# Sequencer-V02-023.net
KiCad netlist of a schematic drawn in EAGLE
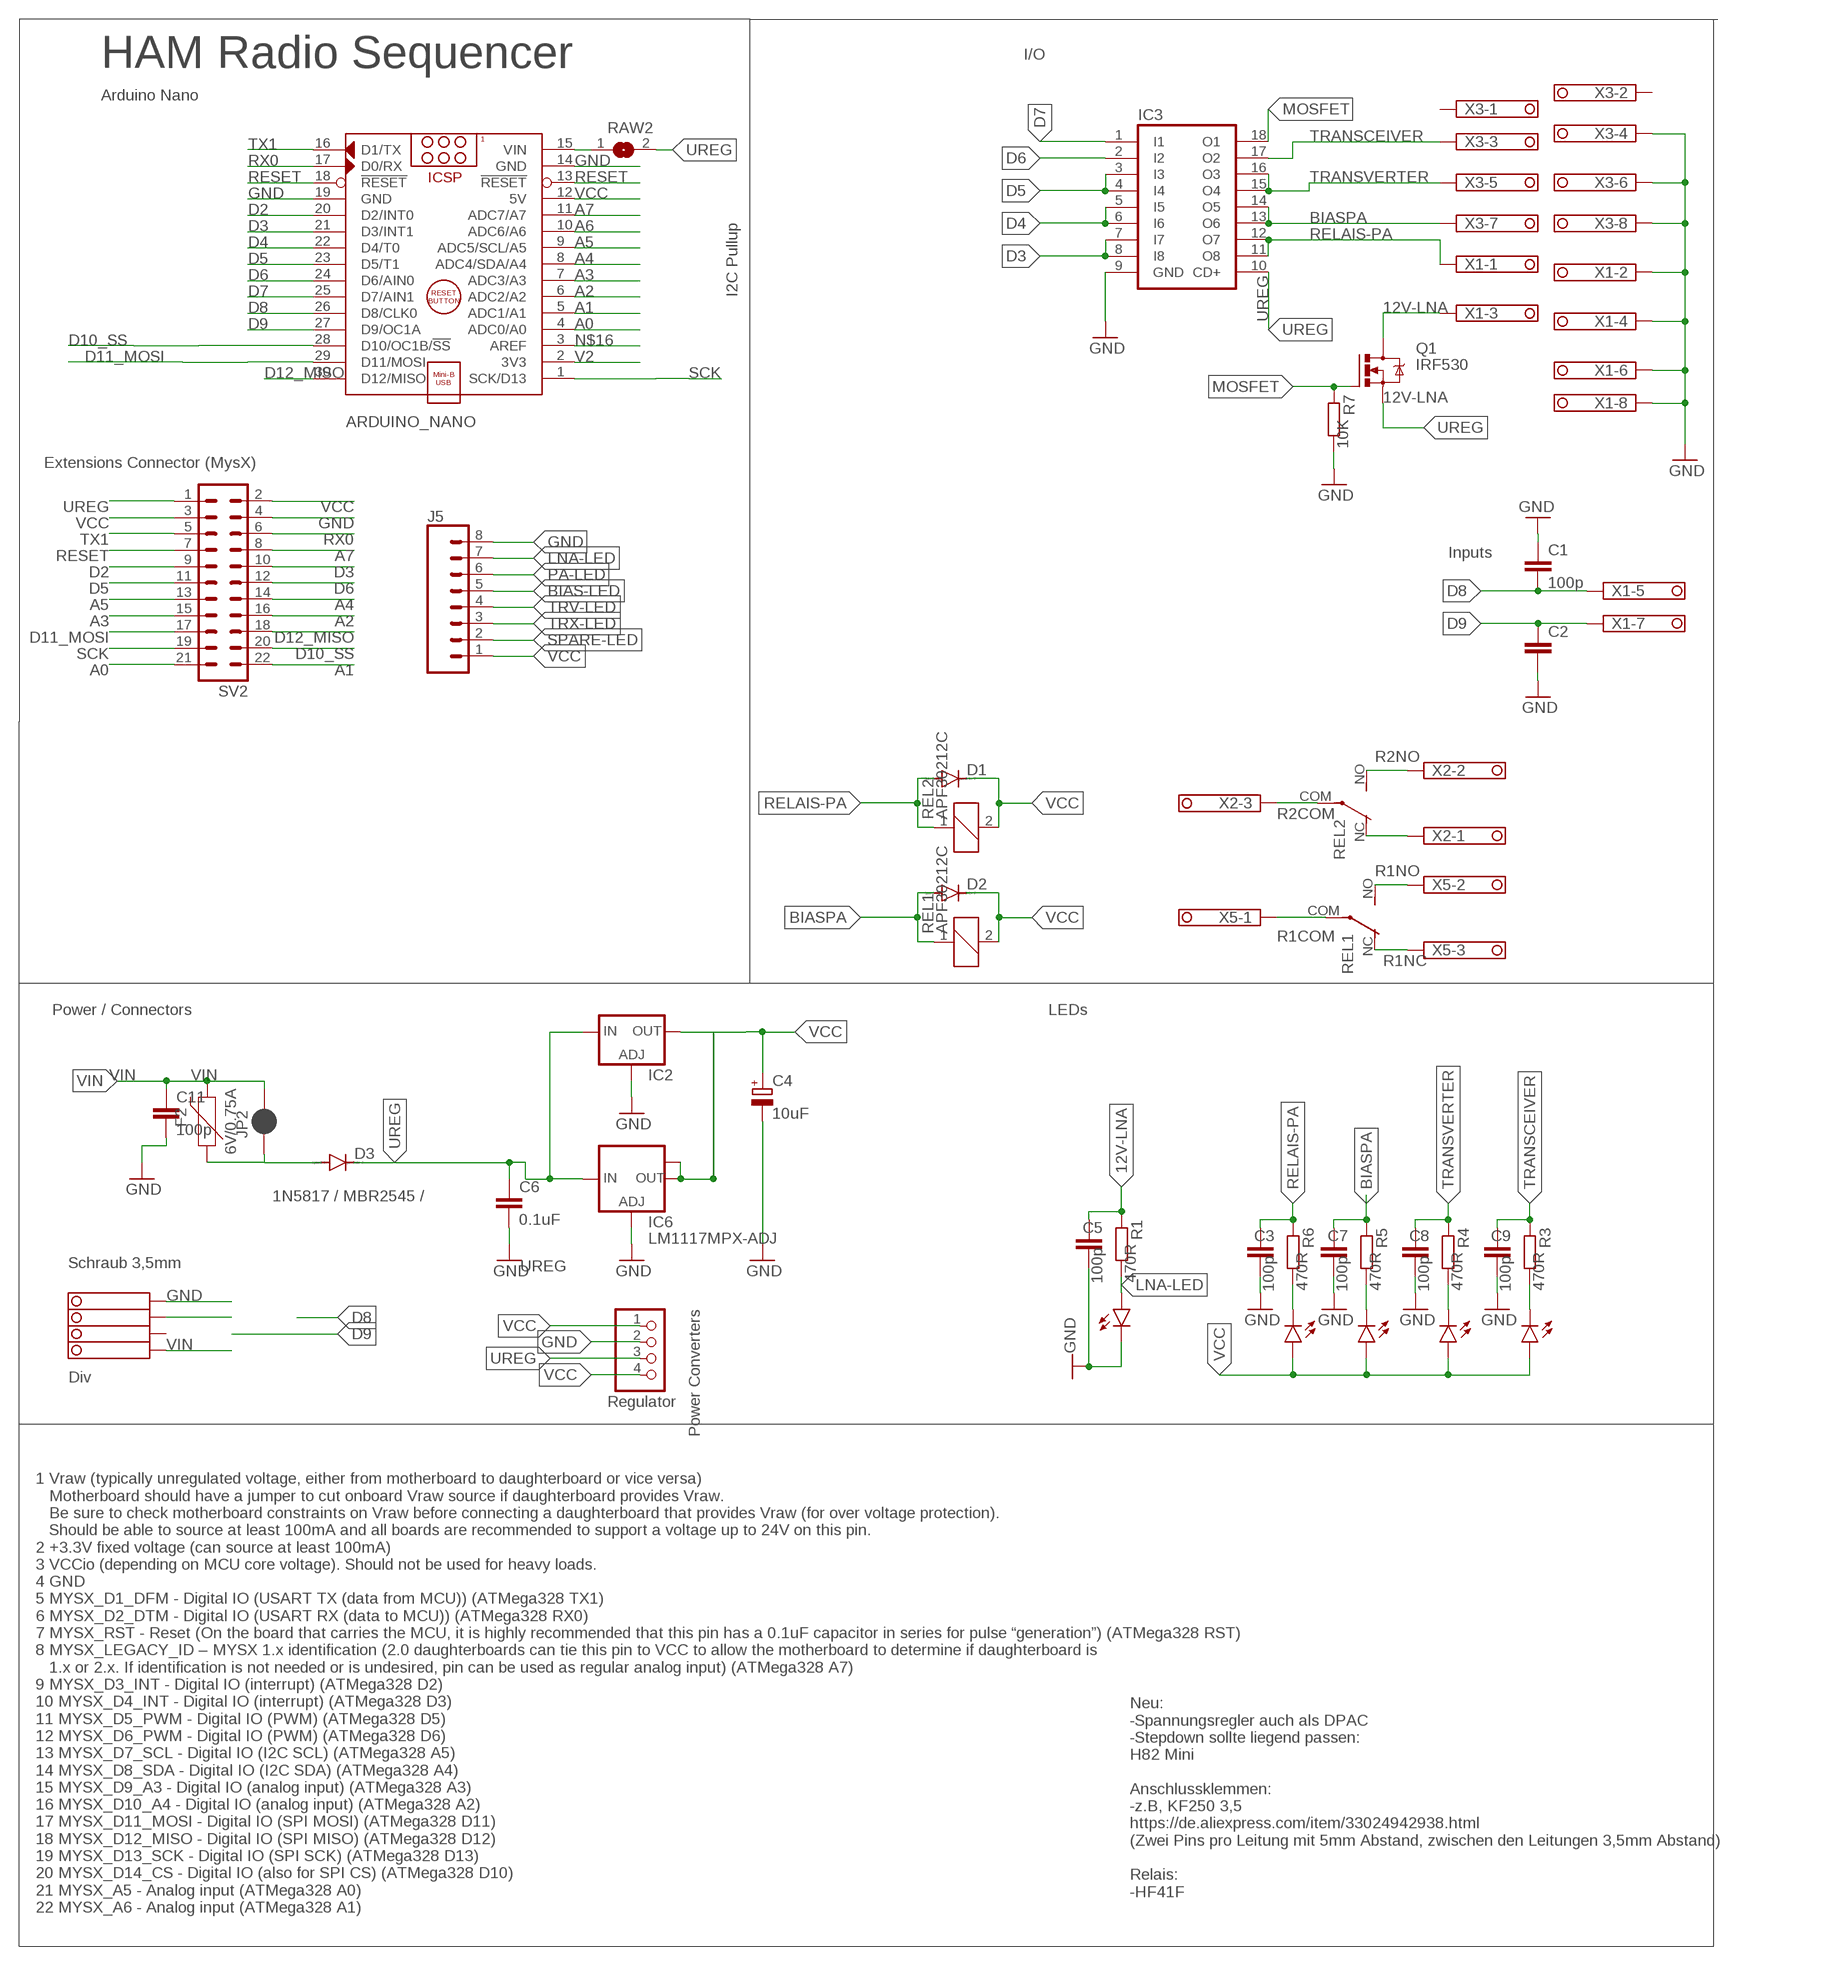
[diagram p0: schematic, sheet 1]

(export (version "E")
  (design (tool "Eeschema 10.0.6"))
  (components
    (comp (ref "ARDUINO_NANO")
      (value "ARDUINO_NANO_OHNE-BOHR")
      (footprint "eagle-import:ARDUINO_NANO")
      (libsource (lib "eagle-import") (part "ARDUINO_NANO_OHNE-BOHR"))
    )
    (comp (ref "C1")
      (value "100p")
      (footprint "eagle-import:C025-025X050")
      (libsource (lib "eagle-import") (part "C-EU025-025X050"))
    )
    (comp (ref "C2")
      (value "C-EU025-025X050")
      (footprint "eagle-import:C025-025X050")
      (libsource (lib "eagle-import") (part "C-EU025-025X050"))
    )
    (comp (ref "C3")
      (value "100p")
      (footprint "eagle-import:C025-025X050")
      (libsource (lib "eagle-import") (part "C-EU025-025X050"))
    )
    (comp (ref "C4")
      (value "10uF")
      (footprint "eagle-import:E3,5-8")
      (libsource (lib "eagle-import") (part "CPOL-EUE3.5-8"))
    )
    (comp (ref "C5")
      (value "100p")
      (footprint "eagle-import:C025-025X050")
      (libsource (lib "eagle-import") (part "C-EU025-025X050"))
    )
    (comp (ref "C6")
      (value "0.1uF")
      (footprint "eagle-import:C050-024X044")
      (libsource (lib "eagle-import") (part "C-EU050-024X044"))
    )
    (comp (ref "C7")
      (value "100p")
      (footprint "eagle-import:C025-025X050")
      (libsource (lib "eagle-import") (part "C-EU025-025X050"))
    )
    (comp (ref "C8")
      (value "100p")
      (footprint "eagle-import:C025-025X050")
      (libsource (lib "eagle-import") (part "C-EU025-025X050"))
    )
    (comp (ref "C9")
      (value "100p")
      (footprint "eagle-import:C025-025X050")
      (libsource (lib "eagle-import") (part "C-EU025-025X050"))
    )
    (comp (ref "C11")
      (value "100p")
      (footprint "eagle-import:C025-025X050")
      (libsource (lib "eagle-import") (part "C-EU025-025X050"))
    )
    (comp (ref "D1")
      (value "DIODE-D-2.5")
      (footprint "eagle-import:D-2.5")
      (libsource (lib "eagle-import") (part "DIODE-D-2.5"))
    )
    (comp (ref "D2")
      (value "DIODE-D-2.5")
      (footprint "eagle-import:D-2.5")
      (libsource (lib "eagle-import") (part "DIODE-D-2.5"))
    )
    (comp (ref "D3")
      (value "1N5817 / MBR2545 /")
      (footprint "eagle-import:D-7.5")
      (libsource (lib "eagle-import") (part "DIODE-D-7.5"))
    )
    (comp (ref "F2")
      (value "6V/0.75A")
      (footprint "eagle-import:1206")
      (libsource (lib "eagle-import") (part "PPTC_THREE-QUARTER-AMP"))
    )
    (comp (ref "IC2")
      (value "LD117ADT50TR")
      (footprint "eagle-import:DPACK")
      (libsource (lib "eagle-import") (part "LD117A?DT50TR"))
    )
    (comp (ref "IC3")
      (value "ULN2803A")
      (footprint "eagle-import:DIL18")
      (libsource (lib "eagle-import") (part "ULN2803A"))
    )
    (comp (ref "IC6")
      (value "LM1117MPX-ADJ")
      (footprint "eagle-import:SOT223")
      (libsource (lib "eagle-import") (part "LM1117MPX-ADJ"))
    )
    (comp (ref "J5")
      (value "CONN_08LOCK")
      (footprint "eagle-import:1X08_LOCK")
      (libsource (lib "eagle-import") (part "CONN_08LOCK"))
    )
    (comp (ref "JP2")
      (value "JUMPER-SMT_2_NC_PASTE_NO-SILK")
      (footprint "eagle-import:SMT-JUMPER_2_NC_PASTE_NO-SILK")
      (libsource (lib "eagle-import") (part "JUMPER-SMT_2_NC_PASTE_NO-SILK"))
    )
    (comp (ref "LED-BIAS")
      (value "LED3MM")
      (footprint "eagle-import:LED3MM")
      (libsource (lib "eagle-import") (part "LED3MM"))
    )
    (comp (ref "LED-LNA")
      (value "LED3MM")
      (footprint "eagle-import:LED3MM")
      (libsource (lib "eagle-import") (part "LED3MM"))
    )
    (comp (ref "LED-PA")
      (value "LED3MM")
      (footprint "eagle-import:LED3MM")
      (libsource (lib "eagle-import") (part "LED3MM"))
    )
    (comp (ref "LED-TRV")
      (value "LED3MM")
      (footprint "eagle-import:LED3MM")
      (libsource (lib "eagle-import") (part "LED3MM"))
    )
    (comp (ref "LED-TRX")
      (value "LED3MM")
      (footprint "eagle-import:LED3MM")
      (libsource (lib "eagle-import") (part "LED3MM"))
    )
    (comp (ref "Q1")
      (value "IRF530")
      (footprint "eagle-import:TO220BV")
      (libsource (lib "eagle-import") (part "IRF530"))
    )
    (comp (ref "R1")
      (value "470R")
      (footprint "eagle-import:0207_7")
      (libsource (lib "eagle-import") (part "R-EU_0207/7"))
    )
    (comp (ref "R3")
      (value "470R")
      (footprint "eagle-import:0207_7")
      (libsource (lib "eagle-import") (part "R-EU_0207/7"))
    )
    (comp (ref "R4")
      (value "470R")
      (footprint "eagle-import:0207_7")
      (libsource (lib "eagle-import") (part "R-EU_0207/7"))
    )
    (comp (ref "R5")
      (value "470R")
      (footprint "eagle-import:0207_7")
      (libsource (lib "eagle-import") (part "R-EU_0207/7"))
    )
    (comp (ref "R6")
      (value "470R")
      (footprint "eagle-import:0207_7")
      (libsource (lib "eagle-import") (part "R-EU_0207/7"))
    )
    (comp (ref "R7")
      (value "10K")
      (footprint "eagle-import:0207_7")
      (libsource (lib "eagle-import") (part "R-EU_0207/7"))
    )
    (comp (ref "RAW2")
      (value "SJ")
      (footprint "eagle-import:SJ")
      (libsource (lib "eagle-import") (part "SJ"))
    )
    (comp (ref "REL1")
      (value "APF30212C")
      (footprint "eagle-import:APF30212C")
      (libsource (lib "eagle-import") (part "APF30212C"))
    )
    (comp (ref "REL2")
      (value "APF30212C")
      (footprint "eagle-import:APF30212C")
      (libsource (lib "eagle-import") (part "APF30212C"))
    )
    (comp (ref "STEPDWN")
      (value "PINHD-1X04_2.54-S")
      (footprint "eagle-import:1X04-S")
      (libsource (lib "eagle-import") (part "PINHD-1X04_2.54-S"))
    )
    (comp (ref "SV2")
      (value "MA11-2")
      (footprint "eagle-import:MA11-2")
      (libsource (lib "eagle-import") (part "MA11-2"))
    )
    (comp (ref "X1")
      (value "MARTIN8X2-1751303")
      (footprint "eagle-import:1751303")
      (libsource (lib "eagle-import") (part "MARTIN8X2-1751303"))
    )
    (comp (ref "X2")
      (value "MARTIN3X2-1751303175L303-3")
      (footprint "eagle-import:1751303-3")
      (libsource (lib "eagle-import") (part "MARTIN3X2-1751303175L303-3"))
    )
    (comp (ref "X3")
      (value "MARTIN8X2-1751303")
      (footprint "eagle-import:1751303")
      (libsource (lib "eagle-import") (part "MARTIN8X2-1751303"))
    )
    (comp (ref "X4")
      (value "1751264")
      (footprint "eagle-import:1751264")
      (libsource (lib "eagle-import") (part "1751264"))
    )
    (comp (ref "X5")
      (value "MARTIN3X2-1751303175L303-3")
      (footprint "eagle-import:1751303-3")
      (libsource (lib "eagle-import") (part "MARTIN3X2-1751303175L303-3"))
    )
  )
  (nets
    (net (code "1") (name "/A0") (class "Default")
      (node (ref "ARDUINO_NANO") (pin "4") (pinfunction "ADC0/A0_4") (pintype "bidirectional"))
      (node (ref "SV2") (pin "21") (pinfunction "21_21") (pintype "passive"))
    )
    (net (code "2") (name "/A1") (class "Default")
      (node (ref "ARDUINO_NANO") (pin "5") (pinfunction "ADC1/A1_5") (pintype "bidirectional"))
      (node (ref "SV2") (pin "22") (pinfunction "22_22") (pintype "passive"))
    )
    (net (code "3") (name "/A2") (class "Default")
      (node (ref "ARDUINO_NANO") (pin "6") (pinfunction "ADC2/A2_6") (pintype "bidirectional"))
      (node (ref "SV2") (pin "16") (pinfunction "16_16") (pintype "passive"))
    )
    (net (code "4") (name "/A3") (class "Default")
      (node (ref "ARDUINO_NANO") (pin "7") (pinfunction "ADC3/A3_7") (pintype "bidirectional"))
      (node (ref "SV2") (pin "15") (pinfunction "15_15") (pintype "passive"))
    )
    (net (code "5") (name "/A4") (class "Default")
      (node (ref "ARDUINO_NANO") (pin "8") (pinfunction "ADC4/SDA/A4_8") (pintype "bidirectional"))
      (node (ref "SV2") (pin "14") (pinfunction "14_14") (pintype "passive"))
    )
    (net (code "6") (name "/A5") (class "Default")
      (node (ref "ARDUINO_NANO") (pin "9") (pinfunction "ADC5/SCL/A5_9") (pintype "bidirectional"))
      (node (ref "SV2") (pin "13") (pinfunction "13_13") (pintype "passive"))
    )
    (net (code "7") (name "/A6") (class "Default")
      (node (ref "ARDUINO_NANO") (pin "10") (pinfunction "ADC6/A6_10") (pintype "bidirectional"))
    )
    (net (code "8") (name "/A7") (class "Default")
      (node (ref "ARDUINO_NANO") (pin "11") (pinfunction "ADC7/A7_11") (pintype "bidirectional"))
      (node (ref "SV2") (pin "8") (pinfunction "8_8") (pintype "passive"))
    )
    (net (code "9") (name "/D2") (class "Default")
      (node (ref "ARDUINO_NANO") (pin "20") (pinfunction "D2/INT0_20") (pintype "bidirectional"))
      (node (ref "SV2") (pin "9") (pinfunction "9_9") (pintype "passive"))
    )
    (net (code "10") (name "/D10_SS") (class "Default")
      (node (ref "ARDUINO_NANO") (pin "28") (pinfunction "D10/OC1B/~{SS}_28") (pintype "bidirectional"))
      (node (ref "SV2") (pin "20") (pinfunction "20_20") (pintype "passive"))
    )
    (net (code "11") (name "/D11_MOSI") (class "Default")
      (node (ref "ARDUINO_NANO") (pin "29") (pinfunction "D11/MOSI_29") (pintype "bidirectional"))
      (node (ref "SV2") (pin "17") (pinfunction "17_17") (pintype "passive"))
    )
    (net (code "12") (name "/D12_MISO") (class "Default")
      (node (ref "ARDUINO_NANO") (pin "30") (pinfunction "D12/MISO_30") (pintype "bidirectional"))
      (node (ref "SV2") (pin "18") (pinfunction "18_18") (pintype "passive"))
    )
    (net (code "13") (name "/N$16") (class "Default")
      (node (ref "ARDUINO_NANO") (pin "3") (pinfunction "AREF_3") (pintype "input"))
    )
    (net (code "14") (name "/R1COM") (class "Default")
      (node (ref "REL1") (pin "COM") (pinfunction "P_COM") (pintype "passive"))
      (node (ref "X5") (pin "1") (pinfunction "K_1") (pintype "passive"))
    )
    (net (code "15") (name "/R1NC") (class "Default")
      (node (ref "REL1") (pin "NC") (pinfunction "O_NC") (pintype "passive"))
      (node (ref "X5") (pin "3") (pinfunction "K_3") (pintype "passive"))
    )
    (net (code "16") (name "/R1NO") (class "Default")
      (node (ref "REL1") (pin "NO") (pinfunction "S_NO") (pintype "passive"))
      (node (ref "X5") (pin "2") (pinfunction "K_2") (pintype "passive"))
    )
    (net (code "17") (name "/R2COM") (class "Default")
      (node (ref "REL2") (pin "COM") (pinfunction "P_COM") (pintype "passive"))
      (node (ref "X2") (pin "3") (pinfunction "K_3") (pintype "passive"))
    )
    (net (code "18") (name "/R2NO") (class "Default")
      (node (ref "REL2") (pin "NO") (pinfunction "S_NO") (pintype "passive"))
      (node (ref "X2") (pin "2") (pinfunction "K_2") (pintype "passive"))
    )
    (net (code "19") (name "/RESET") (class "Default")
      (node (ref "ARDUINO_NANO") (pin "13") (pinfunction "~{RESET}_13") (pintype "input"))
      (node (ref "ARDUINO_NANO") (pin "18") (pinfunction "~{RESET}_18") (pintype "input"))
      (node (ref "SV2") (pin "7") (pinfunction "7_7") (pintype "passive"))
    )
    (net (code "20") (name "/RX0") (class "Default")
      (node (ref "ARDUINO_NANO") (pin "17") (pinfunction "D0/RX_17") (pintype "bidirectional"))
      (node (ref "SV2") (pin "6") (pinfunction "6_6") (pintype "passive"))
    )
    (net (code "21") (name "/SCK") (class "Default")
      (node (ref "ARDUINO_NANO") (pin "1") (pinfunction "SCK/D13_1") (pintype "bidirectional"))
      (node (ref "SV2") (pin "19") (pinfunction "19_19") (pintype "passive"))
    )
    (net (code "22") (name "/TX1") (class "Default")
      (node (ref "ARDUINO_NANO") (pin "16") (pinfunction "D1/TX_16") (pintype "bidirectional"))
      (node (ref "SV2") (pin "5") (pinfunction "5_5") (pintype "passive"))
    )
    (net (code "23") (name "/V2") (class "Default")
      (node (ref "ARDUINO_NANO") (pin "2") (pinfunction "3V3_2") (pintype "output"))
    )
    (net (code "24") (name "12V-LNA") (class "Default")
      (node (ref "C5") (pin "1") (pinfunction "1_1") (pintype "passive"))
      (node (ref "Q1") (pin "D") (pinfunction "D_D") (pintype "passive"))
      (node (ref "R1") (pin "1") (pinfunction "1_1") (pintype "passive"))
      (node (ref "X1") (pin "11") (pinfunction "K_11") (pintype "passive"))
    )
    (net (code "25") (name "BIAS-LED") (class "Default")
      (node (ref "J5") (pin "5") (pinfunction "5_5") (pintype "passive"))
      (node (ref "LED-BIAS") (pin "K") (pinfunction "C_K") (pintype "passive"))
      (node (ref "R5") (pin "2") (pinfunction "2_2") (pintype "passive"))
    )
    (net (code "26") (name "BIASPA") (class "Default")
      (node (ref "C7") (pin "1") (pinfunction "1_1") (pintype "passive"))
      (node (ref "D2") (pin "A") (pinfunction "A_A") (pintype "passive"))
      (node (ref "IC3") (pin "13") (pinfunction "O6_13") (pintype "open_collector"))
      (node (ref "IC3") (pin "14") (pinfunction "O5_14") (pintype "open_collector"))
      (node (ref "R5") (pin "1") (pinfunction "1_1") (pintype "passive"))
      (node (ref "REL1") (pin "1") (pinfunction "1_1") (pintype "passive"))
      (node (ref "X3") (pin "15") (pinfunction "K_15") (pintype "passive"))
    )
    (net (code "27") (name "D3") (class "Default")
      (node (ref "ARDUINO_NANO") (pin "21") (pinfunction "D3/INT1_21") (pintype "bidirectional"))
      (node (ref "IC3") (pin "7") (pinfunction "I7_7") (pintype "input"))
      (node (ref "IC3") (pin "8") (pinfunction "I8_8") (pintype "input"))
      (node (ref "SV2") (pin "10") (pinfunction "10_10") (pintype "passive"))
    )
    (net (code "28") (name "D4") (class "Default")
      (node (ref "ARDUINO_NANO") (pin "22") (pinfunction "D4/T0_22") (pintype "bidirectional"))
      (node (ref "IC3") (pin "5") (pinfunction "I5_5") (pintype "input"))
      (node (ref "IC3") (pin "6") (pinfunction "I6_6") (pintype "input"))
    )
    (net (code "29") (name "D5") (class "Default")
      (node (ref "ARDUINO_NANO") (pin "23") (pinfunction "D5/T1_23") (pintype "bidirectional"))
      (node (ref "IC3") (pin "3") (pinfunction "I3_3") (pintype "input"))
      (node (ref "IC3") (pin "4") (pinfunction "I4_4") (pintype "input"))
      (node (ref "SV2") (pin "11") (pinfunction "11_11") (pintype "passive"))
    )
    (net (code "30") (name "D6") (class "Default")
      (node (ref "ARDUINO_NANO") (pin "24") (pinfunction "D6/AIN0_24") (pintype "bidirectional"))
      (node (ref "IC3") (pin "2") (pinfunction "I2_2") (pintype "input"))
      (node (ref "SV2") (pin "12") (pinfunction "12_12") (pintype "passive"))
    )
    (net (code "31") (name "D7") (class "Default")
      (node (ref "ARDUINO_NANO") (pin "25") (pinfunction "D7/AIN1_25") (pintype "bidirectional"))
      (node (ref "IC3") (pin "1") (pinfunction "I1_1") (pintype "input"))
    )
    (net (code "32") (name "D8") (class "Default")
      (node (ref "ARDUINO_NANO") (pin "26") (pinfunction "D8/CLK0_26") (pintype "bidirectional"))
      (node (ref "C1") (pin "2") (pinfunction "2_2") (pintype "passive"))
      (node (ref "X1") (pin "13") (pinfunction "K_13") (pintype "passive"))
    )
    (net (code "33") (name "D9") (class "Default")
      (node (ref "ARDUINO_NANO") (pin "27") (pinfunction "D9/OC1A_27") (pintype "bidirectional"))
      (node (ref "C2") (pin "1") (pinfunction "1_1") (pintype "passive"))
      (node (ref "X1") (pin "15") (pinfunction "K_15") (pintype "passive"))
    )
    (net (code "34") (name "GND") (class "Default")
      (node (ref "ARDUINO_NANO") (pin "14") (pinfunction "GND_14") (pintype "power_in"))
      (node (ref "ARDUINO_NANO") (pin "19") (pinfunction "GND_19") (pintype "power_in"))
      (node (ref "C1") (pin "1") (pinfunction "1_1") (pintype "passive"))
      (node (ref "C11") (pin "2") (pinfunction "2_2") (pintype "passive"))
      (node (ref "C2") (pin "2") (pinfunction "2_2") (pintype "passive"))
      (node (ref "C3") (pin "2") (pinfunction "2_2") (pintype "passive"))
      (node (ref "C4") (pin "-") (pinfunction "-_-") (pintype "passive"))
      (node (ref "C5") (pin "2") (pinfunction "2_2") (pintype "passive"))
      (node (ref "C6") (pin "2") (pinfunction "2_2") (pintype "passive"))
      (node (ref "C7") (pin "2") (pinfunction "2_2") (pintype "passive"))
      (node (ref "C8") (pin "2") (pinfunction "2_2") (pintype "passive"))
      (node (ref "C9") (pin "2") (pinfunction "2_2") (pintype "passive"))
      (node (ref "IC2") (pin "1") (pinfunction "ADJ_1") (pintype "input"))
      (node (ref "IC3") (pin "9") (pinfunction "GND_9") (pintype "power_in"))
      (node (ref "IC6") (pin "1") (pinfunction "ADJ_1") (pintype "input"))
      (node (ref "J5") (pin "8") (pinfunction "8_8") (pintype "passive"))
      (node (ref "LED-LNA") (pin "K") (pinfunction "C_K") (pintype "passive"))
      (node (ref "R7") (pin "2") (pinfunction "2_2") (pintype "passive"))
      (node (ref "STEPDWN") (pin "2") (pinfunction "2_2") (pintype "passive"))
      (node (ref "SV2") (pin "4") (pinfunction "4_4") (pintype "passive"))
      (node (ref "X1") (pin "10") (pinfunction "K_10") (pintype "passive"))
      (node (ref "X1") (pin "12") (pinfunction "K_12") (pintype "passive"))
      (node (ref "X1") (pin "14") (pinfunction "K_14") (pintype "passive"))
      (node (ref "X1") (pin "16") (pinfunction "K_16") (pintype "passive"))
      (node (ref "X3") (pin "12") (pinfunction "K_12") (pintype "passive"))
      (node (ref "X3") (pin "14") (pinfunction "K_14") (pintype "passive"))
      (node (ref "X3") (pin "16") (pinfunction "K_16") (pintype "passive"))
      (node (ref "X4") (pin "4") (pinfunction "K_4") (pintype "passive"))
    )
    (net (code "35") (name "LNA-LED") (class "Default")
      (node (ref "J5") (pin "7") (pinfunction "7_7") (pintype "passive"))
      (node (ref "LED-LNA") (pin "A") (pinfunction "A_A") (pintype "passive"))
      (node (ref "R1") (pin "2") (pinfunction "2_2") (pintype "passive"))
    )
    (net (code "36") (name "MOSFET") (class "Default")
      (node (ref "IC3") (pin "18") (pinfunction "O1_18") (pintype "open_collector"))
      (node (ref "Q1") (pin "G") (pinfunction "G_G") (pintype "passive"))
      (node (ref "R7") (pin "1") (pinfunction "1_1") (pintype "passive"))
    )
    (net (code "37") (name "Net-(ARDUINO_NANO-VIN)") (class "Default")
      (node (ref "ARDUINO_NANO") (pin "15") (pinfunction "VIN_15") (pintype "power_in"))
      (node (ref "RAW2") (pin "1") (pinfunction "1_1") (pintype "passive"))
    )
    (net (code "38") (name "Net-(D3-PadA)") (class "Default")
      (node (ref "D3") (pin "A") (pinfunction "A_A") (pintype "passive"))
      (node (ref "F2") (pin "1") (pinfunction "1_1") (pintype "bidirectional"))
      (node (ref "JP2") (pin "1") (pinfunction "1_1") (pintype "passive"))
    )
    (net (code "39") (name "Net-(REL2B-O)") (class "Default")
      (node (ref "REL2") (pin "NC") (pinfunction "O_NC") (pintype "passive"))
      (node (ref "X2") (pin "1") (pinfunction "K_1") (pintype "passive"))
    )
    (net (code "40") (name "PA-LED") (class "Default")
      (node (ref "J5") (pin "6") (pinfunction "6_6") (pintype "passive"))
      (node (ref "LED-PA") (pin "K") (pinfunction "C_K") (pintype "passive"))
      (node (ref "R6") (pin "2") (pinfunction "2_2") (pintype "passive"))
    )
    (net (code "41") (name "RELAIS-PA") (class "Default")
      (node (ref "C3") (pin "1") (pinfunction "1_1") (pintype "passive"))
      (node (ref "D1") (pin "A") (pinfunction "A_A") (pintype "passive"))
      (node (ref "IC3") (pin "11") (pinfunction "O8_11") (pintype "open_collector"))
      (node (ref "IC3") (pin "12") (pinfunction "O7_12") (pintype "open_collector"))
      (node (ref "R6") (pin "1") (pinfunction "1_1") (pintype "passive"))
      (node (ref "REL2") (pin "1") (pinfunction "1_1") (pintype "passive"))
      (node (ref "X1") (pin "9") (pinfunction "K_9") (pintype "passive"))
    )
    (net (code "42") (name "SPARE-LED") (class "Default")
      (node (ref "J5") (pin "2") (pinfunction "2_2") (pintype "passive"))
    )
    (net (code "43") (name "TRANSCEIVER") (class "Default")
      (node (ref "C9") (pin "1") (pinfunction "1_1") (pintype "passive"))
      (node (ref "IC3") (pin "17") (pinfunction "O2_17") (pintype "open_collector"))
      (node (ref "R3") (pin "1") (pinfunction "1_1") (pintype "passive"))
      (node (ref "X3") (pin "11") (pinfunction "K_11") (pintype "passive"))
    )
    (net (code "44") (name "TRANSVERTER") (class "Default")
      (node (ref "C8") (pin "1") (pinfunction "1_1") (pintype "passive"))
      (node (ref "IC3") (pin "15") (pinfunction "O4_15") (pintype "open_collector"))
      (node (ref "IC3") (pin "16") (pinfunction "O3_16") (pintype "open_collector"))
      (node (ref "R4") (pin "1") (pinfunction "1_1") (pintype "passive"))
      (node (ref "X3") (pin "13") (pinfunction "K_13") (pintype "passive"))
    )
    (net (code "45") (name "TRV-LED") (class "Default")
      (node (ref "J5") (pin "4") (pinfunction "4_4") (pintype "passive"))
      (node (ref "LED-TRV") (pin "K") (pinfunction "C_K") (pintype "passive"))
      (node (ref "R4") (pin "2") (pinfunction "2_2") (pintype "passive"))
    )
    (net (code "46") (name "TRX-LED") (class "Default")
      (node (ref "J5") (pin "3") (pinfunction "3_3") (pintype "passive"))
      (node (ref "LED-TRX") (pin "K") (pinfunction "C_K") (pintype "passive"))
      (node (ref "R3") (pin "2") (pinfunction "2_2") (pintype "passive"))
    )
    (net (code "47") (name "UREG") (class "Default")
      (node (ref "C6") (pin "1") (pinfunction "1_1") (pintype "passive"))
      (node (ref "D3") (pin "C") (pinfunction "C_C") (pintype "passive"))
      (node (ref "IC2") (pin "3") (pinfunction "IN_3") (pintype "input"))
      (node (ref "IC3") (pin "10") (pinfunction "CD+_10") (pintype "passive"))
      (node (ref "IC6") (pin "3") (pinfunction "IN_3") (pintype "input"))
      (node (ref "Q1") (pin "S") (pinfunction "S_S") (pintype "passive"))
      (node (ref "RAW2") (pin "2") (pinfunction "2_2") (pintype "passive"))
      (node (ref "STEPDWN") (pin "3") (pinfunction "3_3") (pintype "passive"))
      (node (ref "SV2") (pin "1") (pinfunction "1_1") (pintype "passive"))
    )
    (net (code "48") (name "VCC") (class "Default")
      (node (ref "ARDUINO_NANO") (pin "12") (pinfunction "5V_12") (pintype "power_in"))
      (node (ref "C4") (pin "+") (pinfunction "+_+") (pintype "passive"))
      (node (ref "D1") (pin "C") (pinfunction "C_C") (pintype "passive"))
      (node (ref "D2") (pin "C") (pinfunction "C_C") (pintype "passive"))
      (node (ref "IC2") (pin "4") (pinfunction "OUT_4") (pintype "passive"))
      (node (ref "IC6") (pin "2") (pinfunction "OUT_2") (pintype "passive"))
      (node (ref "IC6") (pin "TAB") (pinfunction "OUT1_TAB") (pintype "passive"))
      (node (ref "J5") (pin "1") (pinfunction "1_1") (pintype "passive"))
      (node (ref "LED-BIAS") (pin "A") (pinfunction "A_A") (pintype "passive"))
      (node (ref "LED-PA") (pin "A") (pinfunction "A_A") (pintype "passive"))
      (node (ref "LED-TRV") (pin "A") (pinfunction "A_A") (pintype "passive"))
      (node (ref "LED-TRX") (pin "A") (pinfunction "A_A") (pintype "passive"))
      (node (ref "REL1") (pin "2") (pinfunction "2_2") (pintype "passive"))
      (node (ref "REL2") (pin "2") (pinfunction "2_2") (pintype "passive"))
      (node (ref "STEPDWN") (pin "1") (pinfunction "1_1") (pintype "passive"))
      (node (ref "STEPDWN") (pin "4") (pinfunction "4_4") (pintype "passive"))
      (node (ref "SV2") (pin "2") (pinfunction "2_2") (pintype "passive"))
      (node (ref "SV2") (pin "3") (pinfunction "3_3") (pintype "passive"))
    )
    (net (code "49") (name "VIN") (class "Default")
      (node (ref "C11") (pin "1") (pinfunction "1_1") (pintype "passive"))
      (node (ref "F2") (pin "2") (pinfunction "2_2") (pintype "bidirectional"))
      (node (ref "JP2") (pin "2") (pinfunction "2_2") (pintype "passive"))
      (node (ref "X4") (pin "1") (pinfunction "K_1") (pintype "passive"))
    )
    (net (code "50") (name "unconnected-(X3A-K-Pad9)") (class "Default")
      (node (ref "X3") (pin "9") (pinfunction "K_9") (pintype "passive"))
    )
    (net (code "51") (name "unconnected-(X3B-K-Pad10)") (class "Default")
      (node (ref "X3") (pin "10") (pinfunction "K_10") (pintype "passive"))
    )
    (net (code "52") (name "unconnected-(X4B-K-Pad2)") (class "Default")
      (node (ref "X4") (pin "2") (pinfunction "K_2") (pintype "passive"))
    )
    (net (code "53") (name "unconnected-(X4C-K-Pad3)") (class "Default")
      (node (ref "X4") (pin "3") (pinfunction "K_3") (pintype "passive"))
    )
  )
)
